# led_system.net
KiCad netlist of a schematic drawn in Altium Designer
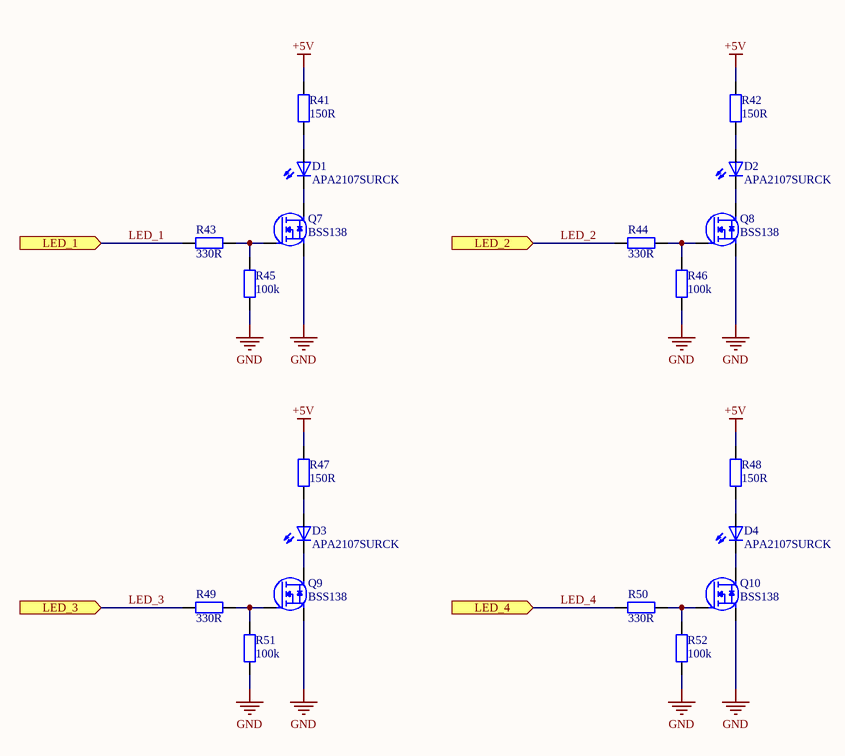
[diagram p0: led_system.SchDoc]

(export (version "E")
  (design (tool "Eeschema 10.0.6"))
  (components
    (comp (ref "D1")
      (value "APA2107SURCK")
      (footprint "LED_0805_RA_INV")
      (description "LED RED CLEAR SMD R/A")
      (fields (field (name "MANUFACTURER") "Kingbright"))
      (libsource (lib "alfasat_parts_lib") (part "APA2107SURCK"))
    )
    (comp (ref "D2")
      (value "APA2107SURCK")
      (footprint "LED_0805_RA")
      (description "LED RED CLEAR SMD R/A")
      (fields (field (name "MANUFACTURER") "Kingbright"))
      (libsource (lib "alfasat_parts_lib") (part "APA2107SURCK"))
    )
    (comp (ref "D3")
      (value "APA2107SURCK")
      (footprint "LED_0805_RA_INV")
      (description "LED RED CLEAR SMD R/A")
      (fields (field (name "MANUFACTURER") "Kingbright"))
      (libsource (lib "alfasat_parts_lib") (part "APA2107SURCK"))
    )
    (comp (ref "D4")
      (value "APA2107SURCK")
      (footprint "LED_0805_RA")
      (description "LED RED CLEAR SMD R/A")
      (fields (field (name "MANUFACTURER") "Kingbright"))
      (libsource (lib "alfasat_parts_lib") (part "APA2107SURCK"))
    )
    (comp (ref "Q7")
      (value "BSS138")
      (footprint "SOT23")
      (description "N-Channel Logic Level Enhancement Mode Field Effect Transistor")
      (fields (field (name "MANUFACTURER") "Diodes Incorporated"))
      (libsource (lib "alfasat_lib") (part "BSS138"))
    )
    (comp (ref "Q8")
      (value "BSS138")
      (footprint "SOT23")
      (description "N-Channel Logic Level Enhancement Mode Field Effect Transistor")
      (fields (field (name "MANUFACTURER") "Diodes Incorporated"))
      (libsource (lib "alfasat_lib") (part "BSS138"))
    )
    (comp (ref "Q9")
      (value "BSS138")
      (footprint "SOT23")
      (description "N-Channel Logic Level Enhancement Mode Field Effect Transistor")
      (fields (field (name "MANUFACTURER") "Diodes Incorporated"))
      (libsource (lib "alfasat_lib") (part "BSS138"))
    )
    (comp (ref "Q10")
      (value "BSS138")
      (footprint "SOT23")
      (description "N-Channel Logic Level Enhancement Mode Field Effect Transistor")
      (fields (field (name "MANUFACTURER") "Diodes Incorporated"))
      (libsource (lib "alfasat_lib") (part "BSS138"))
    )
    (comp (ref "R41")
      (value "150R")
      (footprint "R0603_IPC_MD")
      (description "RES 150 OHM 1% 1/10W 0603")
      (fields
        (field (name "MANUFACTURER") "Stackpole Electronics Inc")
        (field (name "MANUFACTURER PART NUMBER") "RMCF0603FT150R")
      )
      (libsource (lib "alfasat_lib") (part "RMCF0603FT150R"))
    )
    (comp (ref "R42")
      (value "150R")
      (footprint "R0603_IPC_MD")
      (description "RES 150 OHM 1% 1/10W 0603")
      (fields
        (field (name "MANUFACTURER") "Stackpole Electronics Inc")
        (field (name "MANUFACTURER PART NUMBER") "RMCF0603FT150R")
      )
      (libsource (lib "alfasat_lib") (part "RMCF0603FT150R"))
    )
    (comp (ref "R43")
      (value "330R")
      (footprint "R0603_IPC_MD")
      (description "RES SMD 330 OHM 5% 1/10W 0603")
      (fields
        (field (name "MANUFACTURER") "Bourns Inc.")
        (field (name "MANUFACTURER PART NUMBER") "CR0603-JW-331ELF")
      )
      (libsource (lib "alfasat_lib") (part "CR0603-JW-331ELF"))
    )
    (comp (ref "R44")
      (value "330R")
      (footprint "R0603_IPC_MD")
      (description "RES SMD 330 OHM 5% 1/10W 0603")
      (fields
        (field (name "MANUFACTURER") "Bourns Inc.")
        (field (name "MANUFACTURER PART NUMBER") "CR0603-JW-331ELF")
      )
      (libsource (lib "alfasat_lib") (part "CR0603-JW-331ELF"))
    )
    (comp (ref "R45")
      (value "100k")
      (footprint "R0603_IPC_MD")
      (description "RES 100K OHM 1% 1/10W 0603")
      (fields
        (field (name "MANUFACTURER") "Bourns Inc.")
        (field (name "MANUFACTURER PART NUMBER") "RMCF0603FT100K")
      )
      (libsource (lib "alfasat_lib") (part "RMCF0603FT100K"))
    )
    (comp (ref "R46")
      (value "100k")
      (footprint "R0603_IPC_MD")
      (description "RES 100K OHM 1% 1/10W 0603")
      (fields
        (field (name "MANUFACTURER") "Bourns Inc.")
        (field (name "MANUFACTURER PART NUMBER") "RMCF0603FT100K")
      )
      (libsource (lib "alfasat_lib") (part "RMCF0603FT100K"))
    )
    (comp (ref "R47")
      (value "150R")
      (footprint "R0603_IPC_MD")
      (description "RES 150 OHM 1% 1/10W 0603")
      (fields
        (field (name "MANUFACTURER") "Stackpole Electronics Inc")
        (field (name "MANUFACTURER PART NUMBER") "RMCF0603FT150R")
      )
      (libsource (lib "alfasat_lib") (part "RMCF0603FT150R"))
    )
    (comp (ref "R48")
      (value "150R")
      (footprint "R0603_IPC_MD")
      (description "RES 150 OHM 1% 1/10W 0603")
      (fields
        (field (name "MANUFACTURER") "Stackpole Electronics Inc")
        (field (name "MANUFACTURER PART NUMBER") "RMCF0603FT150R")
      )
      (libsource (lib "alfasat_lib") (part "RMCF0603FT150R"))
    )
    (comp (ref "R49")
      (value "330R")
      (footprint "R0603_IPC_MD")
      (description "RES SMD 330 OHM 5% 1/10W 0603")
      (fields
        (field (name "MANUFACTURER") "Bourns Inc.")
        (field (name "MANUFACTURER PART NUMBER") "CR0603-JW-331ELF")
      )
      (libsource (lib "alfasat_lib") (part "CR0603-JW-331ELF"))
    )
    (comp (ref "R50")
      (value "330R")
      (footprint "R0603_IPC_MD")
      (description "RES SMD 330 OHM 5% 1/10W 0603")
      (fields
        (field (name "MANUFACTURER") "Bourns Inc.")
        (field (name "MANUFACTURER PART NUMBER") "CR0603-JW-331ELF")
      )
      (libsource (lib "alfasat_lib") (part "CR0603-JW-331ELF"))
    )
    (comp (ref "R51")
      (value "100k")
      (footprint "R0603_IPC_MD")
      (description "RES 100K OHM 1% 1/10W 0603")
      (fields
        (field (name "MANUFACTURER") "Bourns Inc.")
        (field (name "MANUFACTURER PART NUMBER") "RMCF0603FT100K")
      )
      (libsource (lib "alfasat_lib") (part "RMCF0603FT100K"))
    )
    (comp (ref "R52")
      (value "100k")
      (footprint "R0603_IPC_MD")
      (description "RES 100K OHM 1% 1/10W 0603")
      (fields
        (field (name "MANUFACTURER") "Bourns Inc.")
        (field (name "MANUFACTURER PART NUMBER") "RMCF0603FT100K")
      )
      (libsource (lib "alfasat_lib") (part "RMCF0603FT100K"))
    )
  )
  (nets
    (net (code "1") (name "+5V") (class "Default")
      (node (ref "R41") (pin "2") (pinfunction "2_2") (pintype "passive"))
      (node (ref "R42") (pin "2") (pinfunction "2_2") (pintype "passive"))
      (node (ref "R47") (pin "2") (pinfunction "2_2") (pintype "passive"))
      (node (ref "R48") (pin "2") (pinfunction "2_2") (pintype "passive"))
    )
    (net (code "2") (name "/LED_1") (class "Default")
      (node (ref "R43") (pin "2") (pinfunction "2_2") (pintype "passive"))
    )
    (net (code "3") (name "/LED_2") (class "Default")
      (node (ref "R44") (pin "2") (pinfunction "2_2") (pintype "passive"))
    )
    (net (code "4") (name "/LED_3") (class "Default")
      (node (ref "R49") (pin "2") (pinfunction "2_2") (pintype "passive"))
    )
    (net (code "5") (name "/LED_4") (class "Default")
      (node (ref "R50") (pin "2") (pinfunction "2_2") (pintype "passive"))
    )
    (net (code "6") (name "GND") (class "Default")
      (node (ref "Q10") (pin "2") (pinfunction "S_2") (pintype "passive"))
      (node (ref "Q7") (pin "2") (pinfunction "S_2") (pintype "passive"))
      (node (ref "Q8") (pin "2") (pinfunction "S_2") (pintype "passive"))
      (node (ref "Q9") (pin "2") (pinfunction "S_2") (pintype "passive"))
      (node (ref "R45") (pin "2") (pinfunction "2_2") (pintype "passive"))
      (node (ref "R46") (pin "2") (pinfunction "2_2") (pintype "passive"))
      (node (ref "R51") (pin "2") (pinfunction "2_2") (pintype "passive"))
      (node (ref "R52") (pin "2") (pinfunction "2_2") (pintype "passive"))
    )
    (net (code "7") (name "Net-(D1-A)") (class "Default")
      (node (ref "D1") (pin "2") (pinfunction "A_2") (pintype "passive"))
      (node (ref "R41") (pin "1") (pinfunction "1_1") (pintype "passive"))
    )
    (net (code "8") (name "Net-(D1-C)") (class "Default")
      (node (ref "D1") (pin "1") (pinfunction "C_1") (pintype "passive"))
      (node (ref "Q7") (pin "3") (pinfunction "D_3") (pintype "passive"))
    )
    (net (code "9") (name "Net-(D2-A)") (class "Default")
      (node (ref "D2") (pin "2") (pinfunction "A_2") (pintype "passive"))
      (node (ref "R42") (pin "1") (pinfunction "1_1") (pintype "passive"))
    )
    (net (code "10") (name "Net-(D2-C)") (class "Default")
      (node (ref "D2") (pin "1") (pinfunction "C_1") (pintype "passive"))
      (node (ref "Q8") (pin "3") (pinfunction "D_3") (pintype "passive"))
    )
    (net (code "11") (name "Net-(D3-A)") (class "Default")
      (node (ref "D3") (pin "2") (pinfunction "A_2") (pintype "passive"))
      (node (ref "R47") (pin "1") (pinfunction "1_1") (pintype "passive"))
    )
    (net (code "12") (name "Net-(D3-C)") (class "Default")
      (node (ref "D3") (pin "1") (pinfunction "C_1") (pintype "passive"))
      (node (ref "Q9") (pin "3") (pinfunction "D_3") (pintype "passive"))
    )
    (net (code "13") (name "Net-(D4-A)") (class "Default")
      (node (ref "D4") (pin "2") (pinfunction "A_2") (pintype "passive"))
      (node (ref "R48") (pin "1") (pinfunction "1_1") (pintype "passive"))
    )
    (net (code "14") (name "Net-(D4-C)") (class "Default")
      (node (ref "D4") (pin "1") (pinfunction "C_1") (pintype "passive"))
      (node (ref "Q10") (pin "3") (pinfunction "D_3") (pintype "passive"))
    )
    (net (code "15") (name "Net-(Q7-G)") (class "Default")
      (node (ref "Q7") (pin "1") (pinfunction "G_1") (pintype "passive"))
      (node (ref "R43") (pin "1") (pinfunction "1_1") (pintype "passive"))
      (node (ref "R45") (pin "1") (pinfunction "1_1") (pintype "passive"))
    )
    (net (code "16") (name "Net-(Q8-G)") (class "Default")
      (node (ref "Q8") (pin "1") (pinfunction "G_1") (pintype "passive"))
      (node (ref "R44") (pin "1") (pinfunction "1_1") (pintype "passive"))
      (node (ref "R46") (pin "1") (pinfunction "1_1") (pintype "passive"))
    )
    (net (code "17") (name "Net-(Q9-G)") (class "Default")
      (node (ref "Q9") (pin "1") (pinfunction "G_1") (pintype "passive"))
      (node (ref "R49") (pin "1") (pinfunction "1_1") (pintype "passive"))
      (node (ref "R51") (pin "1") (pinfunction "1_1") (pintype "passive"))
    )
    (net (code "18") (name "Net-(Q10-G)") (class "Default")
      (node (ref "Q10") (pin "1") (pinfunction "G_1") (pintype "passive"))
      (node (ref "R50") (pin "1") (pinfunction "1_1") (pintype "passive"))
      (node (ref "R52") (pin "1") (pinfunction "1_1") (pintype "passive"))
    )
  )
)
